# TestPlatform.net
KiCad netlist of a schematic drawn in EAGLE
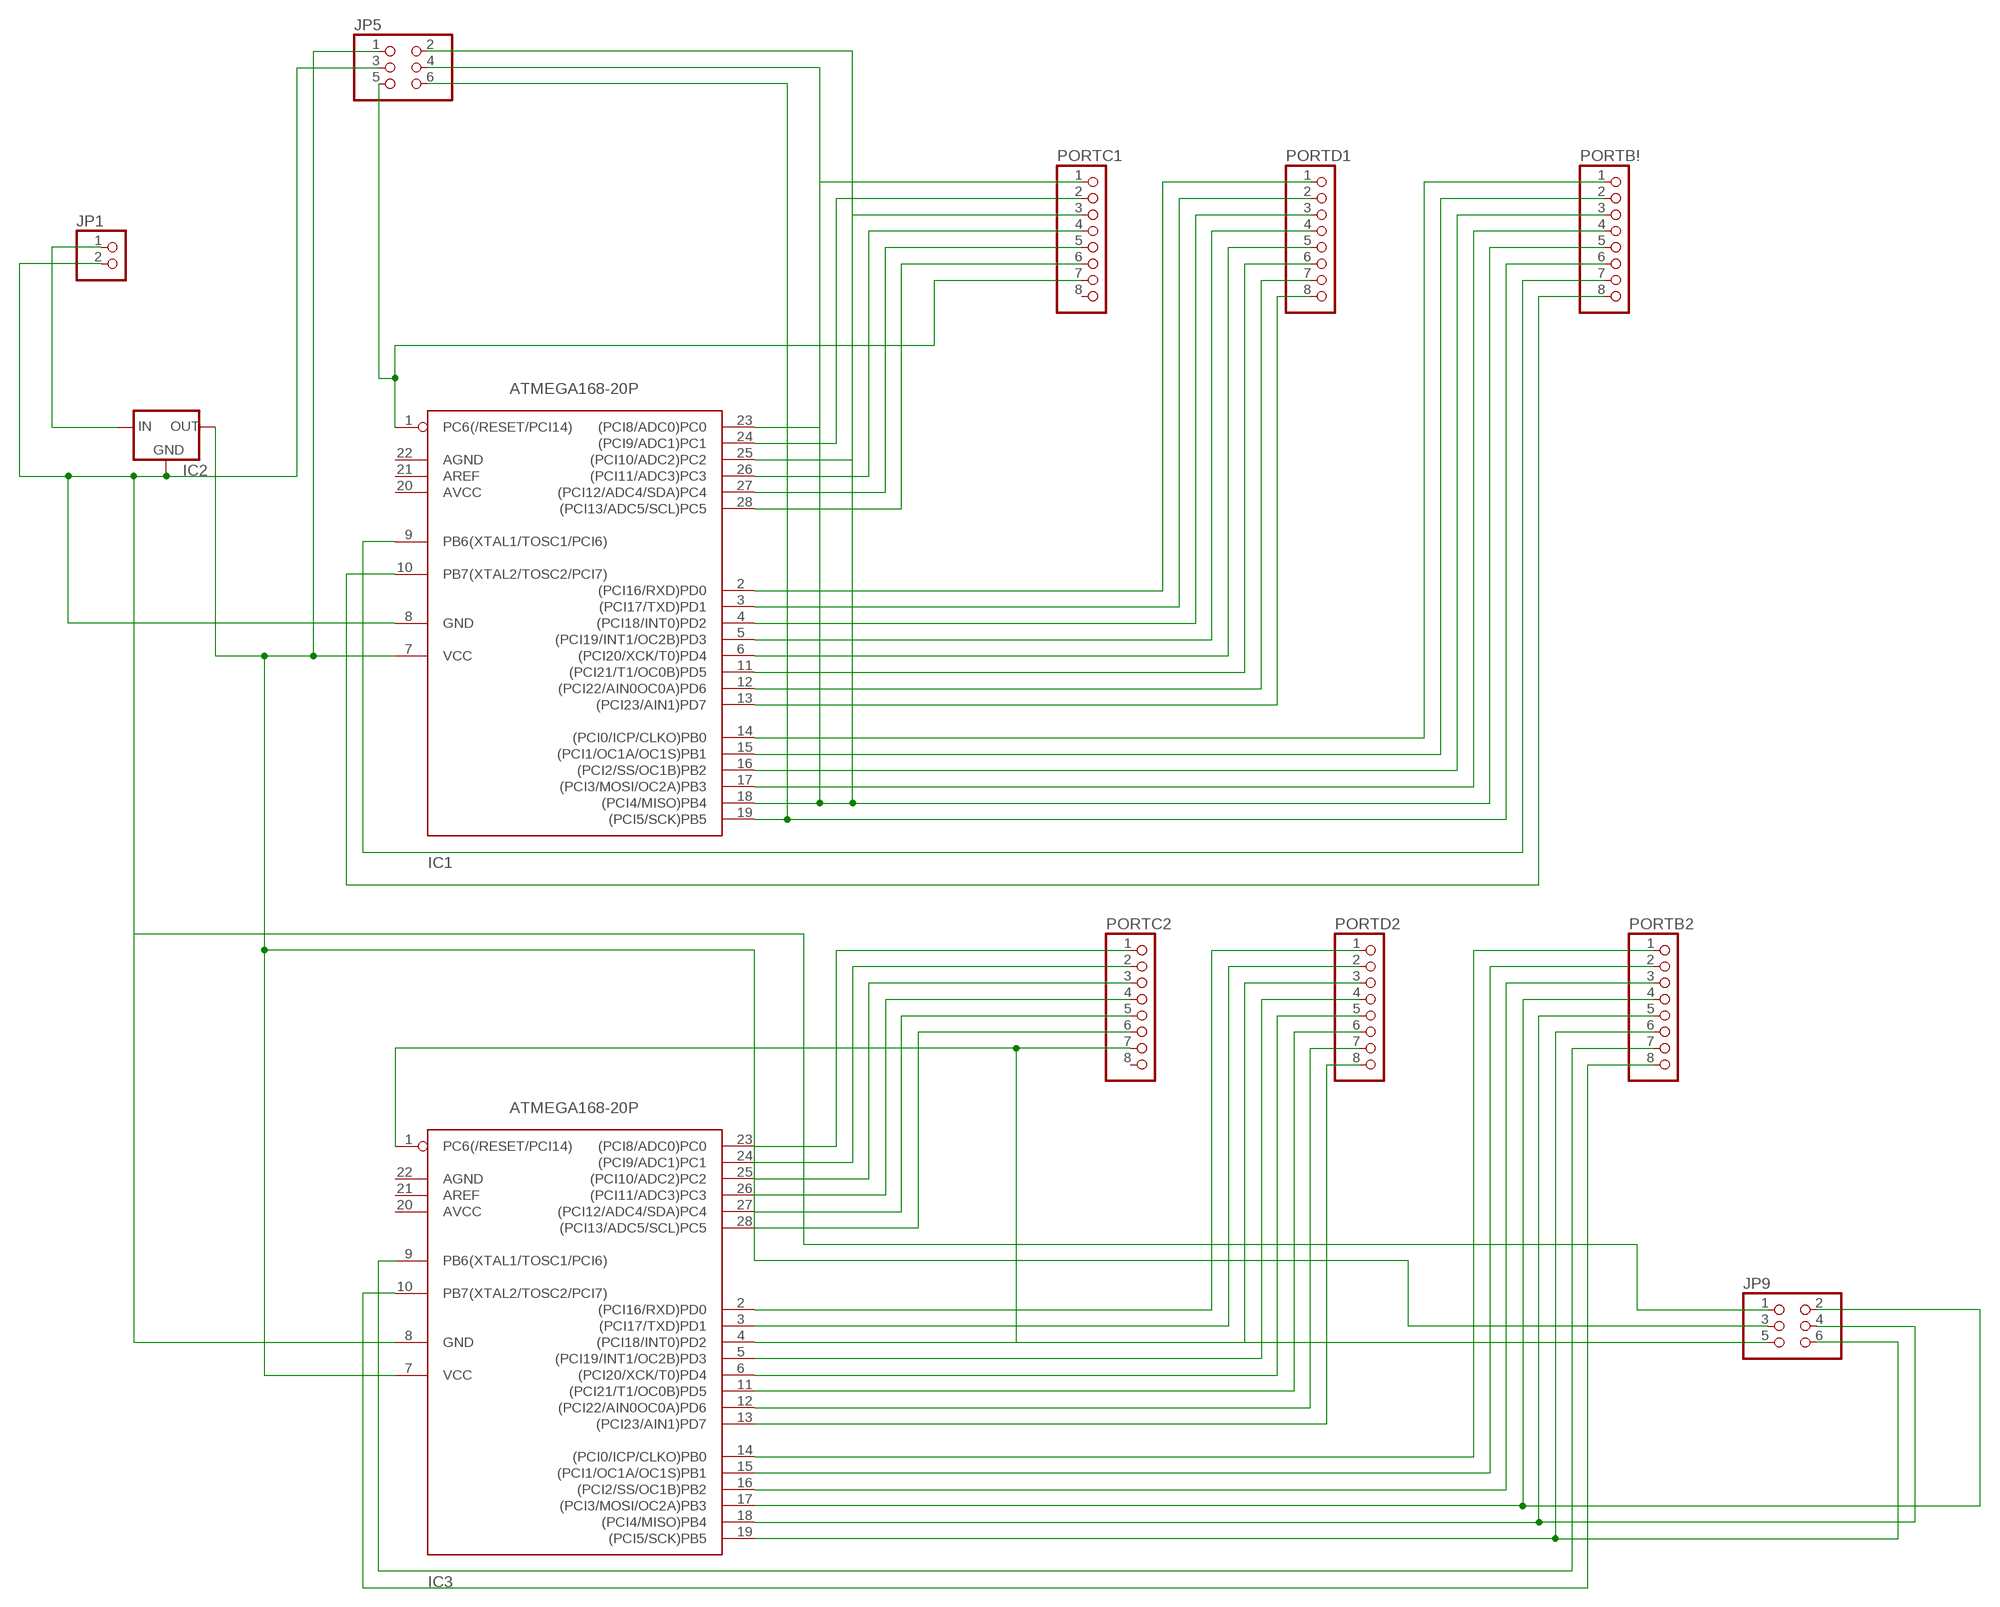
[diagram p0: schematic, sheet 1]

(export (version "E")
  (design (tool "Eeschema 10.0.6"))
  (components
    (comp (ref "IC1")
      (value "ATMEGA168-20P")
      (footprint "eagle-import:DIL28-3")
      (libsource (lib "eagle-import") (part "ATMEGA168P-20"))
    )
    (comp (ref "IC2")
      (value "78XXL")
      (footprint "eagle-import:78XXL")
      (libsource (lib "eagle-import") (part "78XXL"))
    )
    (comp (ref "IC3")
      (value "ATMEGA168-20P")
      (footprint "eagle-import:DIL28-3")
      (libsource (lib "eagle-import") (part "ATMEGA168P-20"))
    )
    (comp (ref "JP1")
      (value "PINHD-1X2")
      (footprint "eagle-import:1X02")
      (libsource (lib "eagle-import") (part "PINHD-1X2"))
    )
    (comp (ref "JP5")
      (value "PINHD-2X3")
      (footprint "eagle-import:2X03")
      (libsource (lib "eagle-import") (part "PINHD-2X3"))
    )
    (comp (ref "JP9")
      (value "PINHD-2X3")
      (footprint "eagle-import:2X03")
      (libsource (lib "eagle-import") (part "PINHD-2X3"))
    )
    (comp (ref "PORTB!")
      (value "PINHD-1X8")
      (footprint "eagle-import:1X08")
      (libsource (lib "eagle-import") (part "PINHD-1X8"))
    )
    (comp (ref "PORTB2")
      (value "PINHD-1X8")
      (footprint "eagle-import:1X08")
      (libsource (lib "eagle-import") (part "PINHD-1X8"))
    )
    (comp (ref "PORTC1")
      (value "PINHD-1X8")
      (footprint "eagle-import:1X08")
      (libsource (lib "eagle-import") (part "PINHD-1X8"))
    )
    (comp (ref "PORTC2")
      (value "PINHD-1X8")
      (footprint "eagle-import:1X08")
      (libsource (lib "eagle-import") (part "PINHD-1X8"))
    )
    (comp (ref "PORTD1")
      (value "PINHD-1X8")
      (footprint "eagle-import:1X08")
      (libsource (lib "eagle-import") (part "PINHD-1X8"))
    )
    (comp (ref "PORTD2")
      (value "PINHD-1X8")
      (footprint "eagle-import:1X08")
      (libsource (lib "eagle-import") (part "PINHD-1X8"))
    )
  )
  (nets
    (net (code "1") (name "Net-(IC1-(PCI0{slash}ICP{slash}CLKO)PB0)") (class "Default")
      (node (ref "IC1") (pin "14") (pinfunction "(PCI0/ICP/CLKO)PB0_14") (pintype "bidirectional"))
      (node (ref "PORTB!") (pin "1") (pinfunction "1_1") (pintype "passive"))
    )
    (net (code "2") (name "Net-(IC1-(PCI1{slash}OC1A{slash}OC1S)PB1)") (class "Default")
      (node (ref "IC1") (pin "15") (pinfunction "(PCI1/OC1A/OC1S)PB1_15") (pintype "bidirectional"))
      (node (ref "PORTB!") (pin "2") (pinfunction "2_2") (pintype "passive"))
    )
    (net (code "3") (name "Net-(IC1-(PCI2{slash}SS{slash}OC1B)PB2)") (class "Default")
      (node (ref "IC1") (pin "16") (pinfunction "(PCI2/SS/OC1B)PB2_16") (pintype "bidirectional"))
      (node (ref "PORTB!") (pin "3") (pinfunction "3_3") (pintype "passive"))
    )
    (net (code "4") (name "Net-(IC1-(PCI3{slash}MOSI{slash}OC2A)PB3)") (class "Default")
      (node (ref "IC1") (pin "17") (pinfunction "(PCI3/MOSI/OC2A)PB3_17") (pintype "bidirectional"))
      (node (ref "PORTB!") (pin "4") (pinfunction "4_4") (pintype "passive"))
    )
    (net (code "5") (name "Net-(IC1-(PCI4{slash}MISO)PB4)") (class "Default")
      (node (ref "IC1") (pin "18") (pinfunction "(PCI4/MISO)PB4_18") (pintype "bidirectional"))
      (node (ref "JP5") (pin "2") (pinfunction "2_2") (pintype "passive"))
      (node (ref "JP5") (pin "4") (pinfunction "4_4") (pintype "passive"))
      (node (ref "PORTB!") (pin "5") (pinfunction "5_5") (pintype "passive"))
    )
    (net (code "6") (name "Net-(IC1-(PCI5{slash}SCK)PB5)") (class "Default")
      (node (ref "IC1") (pin "19") (pinfunction "(PCI5/SCK)PB5_19") (pintype "bidirectional"))
      (node (ref "JP5") (pin "6") (pinfunction "6_6") (pintype "passive"))
      (node (ref "PORTB!") (pin "6") (pinfunction "6_6") (pintype "passive"))
    )
    (net (code "7") (name "Net-(IC1-(PCI8{slash}ADC0)PC0)") (class "Default")
      (node (ref "IC1") (pin "23") (pinfunction "(PCI8/ADC0)PC0_23") (pintype "bidirectional"))
      (node (ref "PORTC1") (pin "1") (pinfunction "1_1") (pintype "passive"))
    )
    (net (code "8") (name "Net-(IC1-(PCI9{slash}ADC1)PC1)") (class "Default")
      (node (ref "IC1") (pin "24") (pinfunction "(PCI9/ADC1)PC1_24") (pintype "bidirectional"))
      (node (ref "PORTC1") (pin "2") (pinfunction "2_2") (pintype "passive"))
    )
    (net (code "9") (name "Net-(IC1-(PCI10{slash}ADC2)PC2)") (class "Default")
      (node (ref "IC1") (pin "25") (pinfunction "(PCI10/ADC2)PC2_25") (pintype "bidirectional"))
      (node (ref "PORTC1") (pin "3") (pinfunction "3_3") (pintype "passive"))
    )
    (net (code "10") (name "Net-(IC1-(PCI11{slash}ADC3)PC3)") (class "Default")
      (node (ref "IC1") (pin "26") (pinfunction "(PCI11/ADC3)PC3_26") (pintype "bidirectional"))
      (node (ref "PORTC1") (pin "4") (pinfunction "4_4") (pintype "passive"))
    )
    (net (code "11") (name "Net-(IC1-(PCI12{slash}ADC4{slash}SDA)PC4)") (class "Default")
      (node (ref "IC1") (pin "27") (pinfunction "(PCI12/ADC4/SDA)PC4_27") (pintype "bidirectional"))
      (node (ref "PORTC1") (pin "5") (pinfunction "5_5") (pintype "passive"))
    )
    (net (code "12") (name "Net-(IC1-(PCI13{slash}ADC5{slash}SCL)PC5)") (class "Default")
      (node (ref "IC1") (pin "28") (pinfunction "(PCI13/ADC5/SCL)PC5_28") (pintype "bidirectional"))
      (node (ref "PORTC1") (pin "6") (pinfunction "6_6") (pintype "passive"))
    )
    (net (code "13") (name "Net-(IC1-(PCI16{slash}RXD)PD0)") (class "Default")
      (node (ref "IC1") (pin "2") (pinfunction "(PCI16/RXD)PD0_2") (pintype "bidirectional"))
      (node (ref "PORTD1") (pin "1") (pinfunction "1_1") (pintype "passive"))
    )
    (net (code "14") (name "Net-(IC1-(PCI17{slash}TXD)PD1)") (class "Default")
      (node (ref "IC1") (pin "3") (pinfunction "(PCI17/TXD)PD1_3") (pintype "bidirectional"))
      (node (ref "PORTD1") (pin "2") (pinfunction "2_2") (pintype "passive"))
    )
    (net (code "15") (name "Net-(IC1-(PCI18{slash}INT0)PD2)") (class "Default")
      (node (ref "IC1") (pin "4") (pinfunction "(PCI18/INT0)PD2_4") (pintype "bidirectional"))
      (node (ref "PORTD1") (pin "3") (pinfunction "3_3") (pintype "passive"))
    )
    (net (code "16") (name "Net-(IC1-(PCI19{slash}INT1{slash}OC2B)PD3)") (class "Default")
      (node (ref "IC1") (pin "5") (pinfunction "(PCI19/INT1/OC2B)PD3_5") (pintype "bidirectional"))
      (node (ref "PORTD1") (pin "4") (pinfunction "4_4") (pintype "passive"))
    )
    (net (code "17") (name "Net-(IC1-(PCI20{slash}XCK{slash}T0)PD4)") (class "Default")
      (node (ref "IC1") (pin "6") (pinfunction "(PCI20/XCK/T0)PD4_6") (pintype "bidirectional"))
      (node (ref "PORTD1") (pin "5") (pinfunction "5_5") (pintype "passive"))
    )
    (net (code "18") (name "Net-(IC1-(PCI21{slash}T1{slash}OC0B)PD5)") (class "Default")
      (node (ref "IC1") (pin "11") (pinfunction "(PCI21/T1/OC0B)PD5_11") (pintype "bidirectional"))
      (node (ref "PORTD1") (pin "6") (pinfunction "6_6") (pintype "passive"))
    )
    (net (code "19") (name "Net-(IC1-(PCI22{slash}AIN0OC0A)PD6)") (class "Default")
      (node (ref "IC1") (pin "12") (pinfunction "(PCI22/AIN0OC0A)PD6_12") (pintype "bidirectional"))
      (node (ref "PORTD1") (pin "7") (pinfunction "7_7") (pintype "passive"))
    )
    (net (code "20") (name "Net-(IC1-(PCI23{slash}AIN1)PD7)") (class "Default")
      (node (ref "IC1") (pin "13") (pinfunction "(PCI23/AIN1)PD7_13") (pintype "bidirectional"))
      (node (ref "PORTD1") (pin "8") (pinfunction "8_8") (pintype "passive"))
    )
    (net (code "21") (name "Net-(IC1-GND)") (class "Default")
      (node (ref "IC1") (pin "8") (pinfunction "GND_8") (pintype "bidirectional"))
      (node (ref "IC2") (pin "GND") (pinfunction "GND_GND") (pintype "input"))
      (node (ref "IC3") (pin "8") (pinfunction "GND_8") (pintype "bidirectional"))
      (node (ref "JP1") (pin "2") (pinfunction "2_2") (pintype "passive"))
      (node (ref "JP5") (pin "3") (pinfunction "3_3") (pintype "passive"))
      (node (ref "JP9") (pin "1") (pinfunction "1_1") (pintype "passive"))
    )
    (net (code "22") (name "Net-(IC1-PB6(XTAL1{slash}TOSC1{slash}PCI6))") (class "Default")
      (node (ref "IC1") (pin "9") (pinfunction "PB6(XTAL1/TOSC1/PCI6)_9") (pintype "bidirectional"))
      (node (ref "PORTB!") (pin "7") (pinfunction "7_7") (pintype "passive"))
    )
    (net (code "23") (name "Net-(IC1-PB7(XTAL2{slash}TOSC2{slash}PCI7))") (class "Default")
      (node (ref "IC1") (pin "10") (pinfunction "PB7(XTAL2/TOSC2/PCI7)_10") (pintype "bidirectional"))
      (node (ref "PORTB!") (pin "8") (pinfunction "8_8") (pintype "passive"))
    )
    (net (code "24") (name "Net-(IC1-PC6({slash}RESET{slash}PCI14))") (class "Default")
      (node (ref "IC1") (pin "1") (pinfunction "PC6(/RESET/PCI14)_1") (pintype "bidirectional"))
      (node (ref "JP5") (pin "5") (pinfunction "5_5") (pintype "passive"))
      (node (ref "PORTC1") (pin "7") (pinfunction "7_7") (pintype "passive"))
    )
    (net (code "25") (name "Net-(IC1-VCC)") (class "Default")
      (node (ref "IC1") (pin "7") (pinfunction "VCC_7") (pintype "bidirectional"))
      (node (ref "IC2") (pin "OUT") (pinfunction "OUT_OUT") (pintype "passive"))
      (node (ref "IC3") (pin "7") (pinfunction "VCC_7") (pintype "bidirectional"))
      (node (ref "JP5") (pin "1") (pinfunction "1_1") (pintype "passive"))
      (node (ref "JP9") (pin "3") (pinfunction "3_3") (pintype "passive"))
    )
    (net (code "26") (name "Net-(IC2-PadIN)") (class "Default")
      (node (ref "IC2") (pin "IN") (pinfunction "IN_IN") (pintype "input"))
      (node (ref "JP1") (pin "1") (pinfunction "1_1") (pintype "passive"))
    )
    (net (code "27") (name "Net-(IC3-(PCI0{slash}ICP{slash}CLKO)PB0)") (class "Default")
      (node (ref "IC3") (pin "14") (pinfunction "(PCI0/ICP/CLKO)PB0_14") (pintype "bidirectional"))
      (node (ref "PORTB2") (pin "1") (pinfunction "1_1") (pintype "passive"))
    )
    (net (code "28") (name "Net-(IC3-(PCI1{slash}OC1A{slash}OC1S)PB1)") (class "Default")
      (node (ref "IC3") (pin "15") (pinfunction "(PCI1/OC1A/OC1S)PB1_15") (pintype "bidirectional"))
      (node (ref "PORTB2") (pin "2") (pinfunction "2_2") (pintype "passive"))
    )
    (net (code "29") (name "Net-(IC3-(PCI2{slash}SS{slash}OC1B)PB2)") (class "Default")
      (node (ref "IC3") (pin "16") (pinfunction "(PCI2/SS/OC1B)PB2_16") (pintype "bidirectional"))
      (node (ref "PORTB2") (pin "3") (pinfunction "3_3") (pintype "passive"))
    )
    (net (code "30") (name "Net-(IC3-(PCI3{slash}MOSI{slash}OC2A)PB3)") (class "Default")
      (node (ref "IC3") (pin "17") (pinfunction "(PCI3/MOSI/OC2A)PB3_17") (pintype "bidirectional"))
      (node (ref "JP9") (pin "2") (pinfunction "2_2") (pintype "passive"))
      (node (ref "PORTB2") (pin "4") (pinfunction "4_4") (pintype "passive"))
    )
    (net (code "31") (name "Net-(IC3-(PCI4{slash}MISO)PB4)") (class "Default")
      (node (ref "IC3") (pin "18") (pinfunction "(PCI4/MISO)PB4_18") (pintype "bidirectional"))
      (node (ref "JP9") (pin "4") (pinfunction "4_4") (pintype "passive"))
      (node (ref "PORTB2") (pin "5") (pinfunction "5_5") (pintype "passive"))
    )
    (net (code "32") (name "Net-(IC3-(PCI5{slash}SCK)PB5)") (class "Default")
      (node (ref "IC3") (pin "19") (pinfunction "(PCI5/SCK)PB5_19") (pintype "bidirectional"))
      (node (ref "JP9") (pin "6") (pinfunction "6_6") (pintype "passive"))
      (node (ref "PORTB2") (pin "6") (pinfunction "6_6") (pintype "passive"))
    )
    (net (code "33") (name "Net-(IC3-(PCI8{slash}ADC0)PC0)") (class "Default")
      (node (ref "IC3") (pin "23") (pinfunction "(PCI8/ADC0)PC0_23") (pintype "bidirectional"))
      (node (ref "PORTC2") (pin "1") (pinfunction "1_1") (pintype "passive"))
    )
    (net (code "34") (name "Net-(IC3-(PCI9{slash}ADC1)PC1)") (class "Default")
      (node (ref "IC3") (pin "24") (pinfunction "(PCI9/ADC1)PC1_24") (pintype "bidirectional"))
      (node (ref "PORTC2") (pin "2") (pinfunction "2_2") (pintype "passive"))
    )
    (net (code "35") (name "Net-(IC3-(PCI10{slash}ADC2)PC2)") (class "Default")
      (node (ref "IC3") (pin "25") (pinfunction "(PCI10/ADC2)PC2_25") (pintype "bidirectional"))
      (node (ref "PORTC2") (pin "3") (pinfunction "3_3") (pintype "passive"))
    )
    (net (code "36") (name "Net-(IC3-(PCI11{slash}ADC3)PC3)") (class "Default")
      (node (ref "IC3") (pin "26") (pinfunction "(PCI11/ADC3)PC3_26") (pintype "bidirectional"))
      (node (ref "PORTC2") (pin "4") (pinfunction "4_4") (pintype "passive"))
    )
    (net (code "37") (name "Net-(IC3-(PCI12{slash}ADC4{slash}SDA)PC4)") (class "Default")
      (node (ref "IC3") (pin "27") (pinfunction "(PCI12/ADC4/SDA)PC4_27") (pintype "bidirectional"))
      (node (ref "PORTC2") (pin "5") (pinfunction "5_5") (pintype "passive"))
    )
    (net (code "38") (name "Net-(IC3-(PCI13{slash}ADC5{slash}SCL)PC5)") (class "Default")
      (node (ref "IC3") (pin "28") (pinfunction "(PCI13/ADC5/SCL)PC5_28") (pintype "bidirectional"))
      (node (ref "PORTC2") (pin "6") (pinfunction "6_6") (pintype "passive"))
    )
    (net (code "39") (name "Net-(IC3-(PCI16{slash}RXD)PD0)") (class "Default")
      (node (ref "IC3") (pin "2") (pinfunction "(PCI16/RXD)PD0_2") (pintype "bidirectional"))
      (node (ref "PORTD2") (pin "1") (pinfunction "1_1") (pintype "passive"))
    )
    (net (code "40") (name "Net-(IC3-(PCI17{slash}TXD)PD1)") (class "Default")
      (node (ref "IC3") (pin "3") (pinfunction "(PCI17/TXD)PD1_3") (pintype "bidirectional"))
      (node (ref "PORTD2") (pin "2") (pinfunction "2_2") (pintype "passive"))
    )
    (net (code "41") (name "Net-(IC3-(PCI18{slash}INT0)PD2)") (class "Default")
      (node (ref "IC3") (pin "4") (pinfunction "(PCI18/INT0)PD2_4") (pintype "bidirectional"))
      (node (ref "PORTD2") (pin "3") (pinfunction "3_3") (pintype "passive"))
    )
    (net (code "42") (name "Net-(IC3-(PCI19{slash}INT1{slash}OC2B)PD3)") (class "Default")
      (node (ref "IC3") (pin "5") (pinfunction "(PCI19/INT1/OC2B)PD3_5") (pintype "bidirectional"))
      (node (ref "PORTD2") (pin "4") (pinfunction "4_4") (pintype "passive"))
    )
    (net (code "43") (name "Net-(IC3-(PCI20{slash}XCK{slash}T0)PD4)") (class "Default")
      (node (ref "IC3") (pin "6") (pinfunction "(PCI20/XCK/T0)PD4_6") (pintype "bidirectional"))
      (node (ref "PORTD2") (pin "5") (pinfunction "5_5") (pintype "passive"))
    )
    (net (code "44") (name "Net-(IC3-(PCI21{slash}T1{slash}OC0B)PD5)") (class "Default")
      (node (ref "IC3") (pin "11") (pinfunction "(PCI21/T1/OC0B)PD5_11") (pintype "bidirectional"))
      (node (ref "PORTD2") (pin "6") (pinfunction "6_6") (pintype "passive"))
    )
    (net (code "45") (name "Net-(IC3-(PCI22{slash}AIN0OC0A)PD6)") (class "Default")
      (node (ref "IC3") (pin "12") (pinfunction "(PCI22/AIN0OC0A)PD6_12") (pintype "bidirectional"))
      (node (ref "PORTD2") (pin "7") (pinfunction "7_7") (pintype "passive"))
    )
    (net (code "46") (name "Net-(IC3-(PCI23{slash}AIN1)PD7)") (class "Default")
      (node (ref "IC3") (pin "13") (pinfunction "(PCI23/AIN1)PD7_13") (pintype "bidirectional"))
      (node (ref "PORTD2") (pin "8") (pinfunction "8_8") (pintype "passive"))
    )
    (net (code "47") (name "Net-(IC3-PB6(XTAL1{slash}TOSC1{slash}PCI6))") (class "Default")
      (node (ref "IC3") (pin "9") (pinfunction "PB6(XTAL1/TOSC1/PCI6)_9") (pintype "bidirectional"))
      (node (ref "PORTB2") (pin "7") (pinfunction "7_7") (pintype "passive"))
    )
    (net (code "48") (name "Net-(IC3-PB7(XTAL2{slash}TOSC2{slash}PCI7))") (class "Default")
      (node (ref "IC3") (pin "10") (pinfunction "PB7(XTAL2/TOSC2/PCI7)_10") (pintype "bidirectional"))
      (node (ref "PORTB2") (pin "8") (pinfunction "8_8") (pintype "passive"))
    )
    (net (code "49") (name "Net-(IC3-PC6({slash}RESET{slash}PCI14))") (class "Default")
      (node (ref "IC3") (pin "1") (pinfunction "PC6(/RESET/PCI14)_1") (pintype "bidirectional"))
      (node (ref "JP9") (pin "5") (pinfunction "5_5") (pintype "passive"))
      (node (ref "PORTC2") (pin "7") (pinfunction "7_7") (pintype "passive"))
    )
    (net (code "50") (name "unconnected-(IC1-AGND-Pad22)") (class "Default")
      (node (ref "IC1") (pin "22") (pinfunction "AGND_22") (pintype "bidirectional"))
    )
    (net (code "51") (name "unconnected-(IC1-AREF-Pad21)") (class "Default")
      (node (ref "IC1") (pin "21") (pinfunction "AREF_21") (pintype "bidirectional"))
    )
    (net (code "52") (name "unconnected-(IC1-AVCC-Pad20)") (class "Default")
      (node (ref "IC1") (pin "20") (pinfunction "AVCC_20") (pintype "bidirectional"))
    )
    (net (code "53") (name "unconnected-(IC3-AGND-Pad22)") (class "Default")
      (node (ref "IC3") (pin "22") (pinfunction "AGND_22") (pintype "bidirectional"))
    )
    (net (code "54") (name "unconnected-(IC3-AREF-Pad21)") (class "Default")
      (node (ref "IC3") (pin "21") (pinfunction "AREF_21") (pintype "bidirectional"))
    )
    (net (code "55") (name "unconnected-(IC3-AVCC-Pad20)") (class "Default")
      (node (ref "IC3") (pin "20") (pinfunction "AVCC_20") (pintype "bidirectional"))
    )
    (net (code "56") (name "unconnected-(PORTC1-Pad8)") (class "Default")
      (node (ref "PORTC1") (pin "8") (pinfunction "8_8") (pintype "passive"))
    )
    (net (code "57") (name "unconnected-(PORTC2-Pad8)") (class "Default")
      (node (ref "PORTC2") (pin "8") (pinfunction "8_8") (pintype "passive"))
    )
  )
)
